# UI_Ticketing_Master.net
KiCad netlist of a schematic drawn in Altium Designer
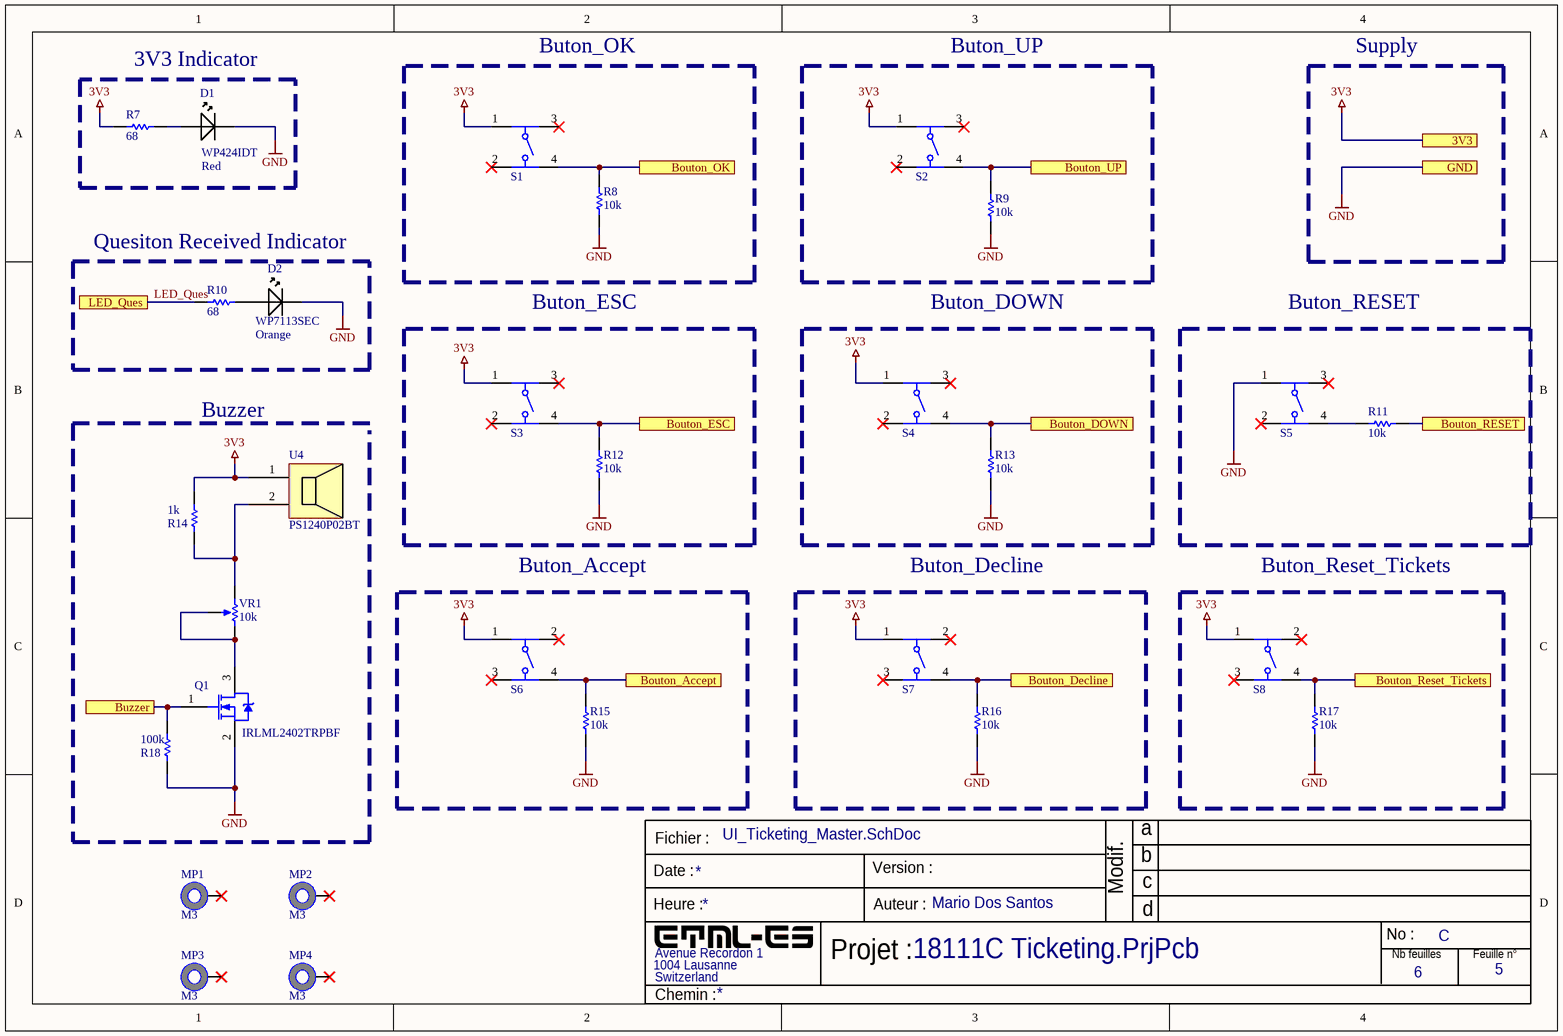
[diagram p0: UI_Ticketing_Master.SchDoc]

(export (version "E")
  (design (tool "Eeschema 10.0.6"))
  (components
    (comp (ref "D1")
      (value "WP424IDT")
      (footprint "LED-2P-2.28-3MM")
      (description "LED")
      (fields (field (name "COLOR") "Red"))
      (libsource (lib "") (part "LED_1"))
    )
    (comp (ref "D2")
      (value "WP7113SEC")
      (footprint "Type 5mm")
      (description "LED")
      (fields (field (name "COLOR") "Orange"))
      (libsource (lib "Spectrometre_Lib") (part "LED"))
    )
    (comp (ref "MP1")
      (value "M3")
      (footprint "PCB_Ticketing_Master:9774010151")
      (description "WA-SMSI SMT Steel Spacer, M2.5 Thread Internal, Length 1mm")
      (libsource (lib "ALTIUM-SMSI_SMT_STEEL_SPACER_M2_5_THREAD_INTERNAL-rev16b") (part "9774010151"))
    )
    (comp (ref "MP2")
      (value "M3")
      (footprint "PCB_Ticketing_Master:9774010151")
      (description "WA-SMSI SMT Steel Spacer, M2.5 Thread Internal, Length 1mm")
      (libsource (lib "ALTIUM-SMSI_SMT_STEEL_SPACER_M2_5_THREAD_INTERNAL-rev16b") (part "9774010151"))
    )
    (comp (ref "MP3")
      (value "M3")
      (footprint "PCB_Ticketing_Master:9774010151")
      (description "WA-SMSI SMT Steel Spacer, M2.5 Thread Internal, Length 1mm")
      (libsource (lib "ALTIUM-SMSI_SMT_STEEL_SPACER_M2_5_THREAD_INTERNAL-rev16b") (part "9774010151"))
    )
    (comp (ref "MP4")
      (value "M3")
      (footprint "PCB_Ticketing_Master:9774010151")
      (description "WA-SMSI SMT Steel Spacer, M2.5 Thread Internal, Length 1mm")
      (libsource (lib "ALTIUM-SMSI_SMT_STEEL_SPACER_M2_5_THREAD_INTERNAL-rev16b") (part "9774010151"))
    )
    (comp (ref "Q1")
      (value "IRLML2402TRPBF")
      (footprint "INTR-IRLML2402TRPBF-3_V")
      (description "HEXFET(R) Power MOSFET, N-Channel, 20 V, 1.2 A, 3-Pin SOT-23, RoHS, Tape and Reel")
      (fields
        (field (name "MANUFACTURER") "Infineon Technologies")
        (field (name "PARTNUMBER") "IRLML2402TRBF")
      )
      (libsource (lib "Altium Content Vault") (part "CMP-2000-05155-1"))
    )
    (comp (ref "R7")
      (value "68")
      (footprint "RESC0805(2012)_L")
      (description "100K 0.125W 5% 0805 (2012 Metric)  SMD")
      (libsource (lib "Altium Content Vault") (part "CMP-1013-00122-1"))
    )
    (comp (ref "R8")
      (value "10k")
      (footprint "RESC0805(2012)_L")
      (description "100K 0.125W 5% 0805 (2012 Metric)  SMD")
      (fields (field (name "TOLERANCE") "5 %") (field (name "POWER") "0.125 W"))
      (libsource (lib "Altium Content Vault") (part "CMP-1013-00122-1"))
    )
    (comp (ref "R9")
      (value "10k")
      (footprint "RESC0805(2012)_L")
      (description "100K 0.125W 5% 0805 (2012 Metric)  SMD")
      (fields (field (name "TOLERANCE") "5 %") (field (name "POWER") "0.125 W"))
      (libsource (lib "Altium Content Vault") (part "CMP-1013-00122-1"))
    )
    (comp (ref "R10")
      (value "68")
      (footprint "RESC0805(2012)_L")
      (description "100K 0.125W 5% 0805 (2012 Metric)  SMD")
      (fields (field (name "TOLERANCE") "5 %") (field (name "POWER") "0.125 W"))
      (libsource (lib "Altium Content Vault") (part "CMP-1013-00122-1"))
    )
    (comp (ref "R11")
      (value "10k")
      (footprint "RESC0805(2012)_L")
      (description "100K 0.125W 5% 0805 (2012 Metric)  SMD")
      (fields (field (name "TOLERANCE") "5 %") (field (name "POWER") "0.125 W"))
      (libsource (lib "Altium Content Vault") (part "CMP-1013-00122-1"))
    )
    (comp (ref "R12")
      (value "10k")
      (footprint "RESC0805(2012)_L")
      (description "100K 0.125W 5% 0805 (2012 Metric)  SMD")
      (fields (field (name "TOLERANCE") "5 %") (field (name "POWER") "0.125 W"))
      (libsource (lib "Altium Content Vault") (part "CMP-1013-00122-1"))
    )
    (comp (ref "R13")
      (value "10k")
      (footprint "RESC0805(2012)_L")
      (description "100K 0.125W 5% 0805 (2012 Metric)  SMD")
      (fields (field (name "TOLERANCE") "5 %") (field (name "POWER") "0.125 W"))
      (libsource (lib "Altium Content Vault") (part "CMP-1013-00122-1"))
    )
    (comp (ref "R14")
      (value "1k")
      (footprint "RESC2013X60X35ML10T20")
      (description "Chip Resistor, 1 KOhm, +/- 1%, 125 mW, -55 to 155 degC, 0805 (2012 Metric), RoHS, Tape and Reel")
      (libsource (lib "Altium Content Vault") (part "CMP-2100-03671-1"))
    )
    (comp (ref "R15")
      (value "10k")
      (footprint "RESC0805(2012)_L")
      (description "100K 0.125W 5% 0805 (2012 Metric)  SMD")
      (fields (field (name "TOLERANCE") "5 %") (field (name "POWER") "0.125 W"))
      (libsource (lib "Altium Content Vault") (part "CMP-1013-00122-1"))
    )
    (comp (ref "R16")
      (value "10k")
      (footprint "RESC0805(2012)_L")
      (description "100K 0.125W 5% 0805 (2012 Metric)  SMD")
      (fields (field (name "TOLERANCE") "5 %") (field (name "POWER") "0.125 W"))
      (libsource (lib "Altium Content Vault") (part "CMP-1013-00122-1"))
    )
    (comp (ref "R17")
      (value "10k")
      (footprint "RESC0805(2012)_L")
      (description "100K 0.125W 5% 0805 (2012 Metric)  SMD")
      (fields (field (name "TOLERANCE") "5 %") (field (name "POWER") "0.125 W"))
      (libsource (lib "Altium Content Vault") (part "CMP-1013-00122-1"))
    )
    (comp (ref "R18")
      (value "100k")
      (footprint "RESC2013X60X35ML10T20")
      (description "Chip Resistor, 100 KOhm, +/- 1%, 125 mW, -55 to 155 degC, 0805 (2012 Metric), RoHS, Tape and Reel")
      (libsource (lib "Altium Content Vault") (part "CMP-2100-03671-1"))
    )
    (comp (ref "S1")
      (value "430152095826")
      (footprint "430152095826")
      (description "6x6mm SMD Tact Switch WS-TASV, height 9.5 mm, 260 gf")
      (fields (field (name "PART NUMBER") "732-6999-1-ND") (field (name "PUBLISHER") "Wurth Elektronik"))
      (libsource (lib "ALTIUM-WS-TASV-rev17b") (part "430152095826"))
    )
    (comp (ref "S2")
      (value "430152095826")
      (footprint "430152095826")
      (description "6x6mm SMD Tact Switch WS-TASV, height 9.5 mm, 260 gf")
      (fields (field (name "PART NUMBER") "732-6999-1-ND") (field (name "PUBLISHER") "Wurth Elektronik"))
      (libsource (lib "ALTIUM-WS-TASV-rev17b") (part "430152095826"))
    )
    (comp (ref "S3")
      (value "430152095826")
      (footprint "430152095826")
      (description "6x6mm SMD Tact Switch WS-TASV, height 9.5 mm, 260 gf")
      (fields (field (name "PART NUMBER") "732-6999-1-ND") (field (name "PUBLISHER") "Wurth Elektronik"))
      (libsource (lib "ALTIUM-WS-TASV-rev17b") (part "430152095826"))
    )
    (comp (ref "S4")
      (value "430152095826")
      (footprint "430152095826")
      (description "6x6mm SMD Tact Switch WS-TASV, height 9.5 mm, 260 gf")
      (fields (field (name "PART NUMBER") "732-6999-1-ND") (field (name "PUBLISHER") "Wurth Elektronik"))
      (libsource (lib "ALTIUM-WS-TASV-rev17b") (part "430152095826"))
    )
    (comp (ref "S5")
      (value "430182050816")
      (footprint "430182050816")
      (description "6x6mm SMD Tact Switch WS-TASV, height 5 mm, 160 gf")
      (fields (field (name "PART NUMBER") "732-7005-1-ND") (field (name "PUBLISHER") "Wurth Elektronik"))
      (libsource (lib "ALTIUM-WS-TASV-rev17b") (part "430182050816"))
    )
    (comp (ref "S6")
      (value "430466073726")
      (footprint "4304x60737x6_12x12x7.3")
      (description "WS-TATV 12x12mm washable Tact Switch, THT version")
      (fields (field (name "PART NUMBER") "430466073726-ND") (field (name "PUBLISHER") "Wurth Elektronik"))
      (libsource (lib "ALTIUM-WS-TATV-rev17a") (part "430466073726"))
    )
    (comp (ref "S7")
      (value "430466073726")
      (footprint "4304x60737x6_12x12x7.3")
      (description "WS-TATV 12x12mm washable Tact Switch, THT version")
      (fields (field (name "PART NUMBER") "430466073726-ND") (field (name "PUBLISHER") "Wurth Elektronik"))
      (libsource (lib "ALTIUM-WS-TATV-rev17a") (part "430466073726"))
    )
    (comp (ref "S8")
      (value "430466073726")
      (footprint "4304x60737x6_12x12x7.3")
      (description "WS-TATV 12x12mm washable Tact Switch, THT version")
      (fields (field (name "PART NUMBER") "430466073726-ND") (field (name "PUBLISHER") "Wurth Elektronik"))
      (libsource (lib "ALTIUM-WS-TATV-rev17a") (part "430466073726"))
    )
    (comp (ref "U4")
      (value "PS1240P02BT")
      (footprint "Buzzer")
      (description "Buzzer 12mm piezo")
      (fields (field (name "MANUFACTURER") "TDK Corporation"))
      (libsource (lib "Schlib1") (part "BZR"))
    )
    (comp (ref "VR1")
      (value "10k")
      (footprint "BOUR-3362P")
      (description "Square Trimpot(R) Trimming Potentiometer, 100 KOhm, 300 V, -55 to 125 degC, 3-Pin THD, RoHS, Tube")
      (fields (field (name "TOLERANCE") "1%") (field (name "PART NUMBER") "3362P-103LF-ND"))
      (libsource (lib "Altium Content Vault") (part "CMP-1747-00003-1"))
    )
  )
  (nets
    (net (code "1") (name "/Bouton_Accept") (class "Default")
      (node (ref "R15") (pin "1") (pinfunction "1_1") (pintype "passive"))
      (node (ref "S6") (pin "4") (pinfunction "4_4") (pintype "passive"))
    )
    (net (code "2") (name "/Bouton_DOWN") (class "Default")
      (node (ref "R13") (pin "1") (pinfunction "1_1") (pintype "passive"))
      (node (ref "S4") (pin "4") (pinfunction "4_4") (pintype "passive"))
    )
    (net (code "3") (name "/Bouton_Decline") (class "Default")
      (node (ref "R16") (pin "1") (pinfunction "1_1") (pintype "passive"))
      (node (ref "S7") (pin "4") (pinfunction "4_4") (pintype "passive"))
    )
    (net (code "4") (name "/Bouton_ESC") (class "Default")
      (node (ref "R12") (pin "1") (pinfunction "1_1") (pintype "passive"))
      (node (ref "S3") (pin "4") (pinfunction "4_4") (pintype "passive"))
    )
    (net (code "5") (name "/Bouton_OK") (class "Default")
      (node (ref "R8") (pin "1") (pinfunction "1_1") (pintype "passive"))
      (node (ref "S1") (pin "4") (pinfunction "4_4") (pintype "passive"))
    )
    (net (code "6") (name "/Bouton_RESET") (class "Default")
      (node (ref "R11") (pin "2") (pinfunction "2_2") (pintype "passive"))
    )
    (net (code "7") (name "/Bouton_Reset_Tickets") (class "Default")
      (node (ref "R17") (pin "1") (pinfunction "1_1") (pintype "passive"))
      (node (ref "S8") (pin "4") (pinfunction "4_4") (pintype "passive"))
    )
    (net (code "8") (name "/Bouton_UP") (class "Default")
      (node (ref "R9") (pin "1") (pinfunction "1_1") (pintype "passive"))
      (node (ref "S2") (pin "4") (pinfunction "4_4") (pintype "passive"))
    )
    (net (code "9") (name "/Buzzer") (class "Default")
      (node (ref "Q1") (pin "1") (pinfunction "G_1") (pintype "passive"))
      (node (ref "R18") (pin "2") (pinfunction "2_2") (pintype "passive"))
    )
    (net (code "10") (name "/LED_Ques") (class "Default")
      (node (ref "R10") (pin "2") (pinfunction "2_2") (pintype "passive"))
    )
    (net (code "11") (name "3V3") (class "Default")
      (node (ref "R14") (pin "2") (pinfunction "2_2") (pintype "passive"))
      (node (ref "R7") (pin "2") (pinfunction "2_2") (pintype "passive"))
      (node (ref "S1") (pin "1") (pinfunction "1_1") (pintype "passive"))
      (node (ref "S2") (pin "1") (pinfunction "1_1") (pintype "passive"))
      (node (ref "S3") (pin "1") (pinfunction "1_1") (pintype "passive"))
      (node (ref "S4") (pin "1") (pinfunction "1_1") (pintype "passive"))
      (node (ref "S6") (pin "1") (pinfunction "1_1") (pintype "passive"))
      (node (ref "S7") (pin "1") (pinfunction "1_1") (pintype "passive"))
      (node (ref "S8") (pin "1") (pinfunction "1_1") (pintype "passive"))
      (node (ref "U4") (pin "1") (pintype "passive"))
    )
    (net (code "12") (name "GND") (class "Default")
      (node (ref "D1") (pin "2") (pinfunction "Cathode_2") (pintype "passive"))
      (node (ref "D2") (pin "1") (pinfunction "Cathode_1") (pintype "passive"))
      (node (ref "Q1") (pin "2") (pinfunction "S_2") (pintype "passive"))
      (node (ref "R12") (pin "2") (pinfunction "2_2") (pintype "passive"))
      (node (ref "R13") (pin "2") (pinfunction "2_2") (pintype "passive"))
      (node (ref "R15") (pin "2") (pinfunction "2_2") (pintype "passive"))
      (node (ref "R16") (pin "2") (pinfunction "2_2") (pintype "passive"))
      (node (ref "R17") (pin "2") (pinfunction "2_2") (pintype "passive"))
      (node (ref "R18") (pin "1") (pinfunction "1_1") (pintype "passive"))
      (node (ref "R8") (pin "2") (pinfunction "2_2") (pintype "passive"))
      (node (ref "R9") (pin "2") (pinfunction "2_2") (pintype "passive"))
      (node (ref "S5") (pin "1") (pinfunction "1_1") (pintype "passive"))
    )
    (net (code "13") (name "Net-(D1-Anode)") (class "Default")
      (node (ref "D1") (pin "1") (pinfunction "Anode_1") (pintype "passive"))
      (node (ref "R7") (pin "1") (pinfunction "1_1") (pintype "passive"))
    )
    (net (code "14") (name "Net-(D2-Anode)") (class "Default")
      (node (ref "D2") (pin "2") (pinfunction "Anode_2") (pintype "passive"))
      (node (ref "R10") (pin "1") (pinfunction "1_1") (pintype "passive"))
    )
    (net (code "15") (name "Net-(Q1-D)") (class "Default")
      (node (ref "Q1") (pin "3") (pinfunction "D_3") (pintype "passive"))
      (node (ref "VR1") (pin "2") (pinfunction "S_2") (pintype "passive"))
      (node (ref "VR1") (pin "3") (pinfunction "CW_3") (pintype "passive"))
    )
    (net (code "16") (name "Net-(R11-Pad1)") (class "Default")
      (node (ref "R11") (pin "1") (pinfunction "1_1") (pintype "passive"))
      (node (ref "S5") (pin "4") (pinfunction "4_4") (pintype "passive"))
    )
    (net (code "17") (name "Net-(VR1-CCW)") (class "Default")
      (node (ref "R14") (pin "1") (pinfunction "1_1") (pintype "passive"))
      (node (ref "U4") (pin "2") (pintype "passive"))
      (node (ref "VR1") (pin "1") (pinfunction "CCW_1") (pintype "passive"))
    )
    (net (code "18") (name "unconnected-(MP1-Pad1)") (class "Default")
      (node (ref "MP1") (pin "1") (pinfunction "1_1") (pintype "passive+no_connect"))
    )
    (net (code "19") (name "unconnected-(MP2-Pad1)") (class "Default")
      (node (ref "MP2") (pin "1") (pinfunction "1_1") (pintype "passive+no_connect"))
    )
    (net (code "20") (name "unconnected-(MP3-Pad1)") (class "Default")
      (node (ref "MP3") (pin "1") (pinfunction "1_1") (pintype "passive+no_connect"))
    )
    (net (code "21") (name "unconnected-(MP4-Pad1)") (class "Default")
      (node (ref "MP4") (pin "1") (pinfunction "1_1") (pintype "passive+no_connect"))
    )
    (net (code "22") (name "unconnected-(S1-Pad2)") (class "Default")
      (node (ref "S1") (pin "2") (pinfunction "2_2") (pintype "passive+no_connect"))
    )
    (net (code "23") (name "unconnected-(S1-Pad3)") (class "Default")
      (node (ref "S1") (pin "3") (pinfunction "3_3") (pintype "passive+no_connect"))
    )
    (net (code "24") (name "unconnected-(S2-Pad2)") (class "Default")
      (node (ref "S2") (pin "2") (pinfunction "2_2") (pintype "passive+no_connect"))
    )
    (net (code "25") (name "unconnected-(S2-Pad3)") (class "Default")
      (node (ref "S2") (pin "3") (pinfunction "3_3") (pintype "passive+no_connect"))
    )
    (net (code "26") (name "unconnected-(S3-Pad2)") (class "Default")
      (node (ref "S3") (pin "2") (pinfunction "2_2") (pintype "passive+no_connect"))
    )
    (net (code "27") (name "unconnected-(S3-Pad3)") (class "Default")
      (node (ref "S3") (pin "3") (pinfunction "3_3") (pintype "passive+no_connect"))
    )
    (net (code "28") (name "unconnected-(S4-Pad2)") (class "Default")
      (node (ref "S4") (pin "2") (pinfunction "2_2") (pintype "passive+no_connect"))
    )
    (net (code "29") (name "unconnected-(S4-Pad3)") (class "Default")
      (node (ref "S4") (pin "3") (pinfunction "3_3") (pintype "passive+no_connect"))
    )
    (net (code "30") (name "unconnected-(S5-Pad2)") (class "Default")
      (node (ref "S5") (pin "2") (pinfunction "2_2") (pintype "passive+no_connect"))
    )
    (net (code "31") (name "unconnected-(S5-Pad3)") (class "Default")
      (node (ref "S5") (pin "3") (pinfunction "3_3") (pintype "passive+no_connect"))
    )
    (net (code "32") (name "unconnected-(S6-Pad2)") (class "Default")
      (node (ref "S6") (pin "2") (pinfunction "2_2") (pintype "passive+no_connect"))
    )
    (net (code "33") (name "unconnected-(S6-Pad3)") (class "Default")
      (node (ref "S6") (pin "3") (pinfunction "3_3") (pintype "passive+no_connect"))
    )
    (net (code "34") (name "unconnected-(S7-Pad2)") (class "Default")
      (node (ref "S7") (pin "2") (pinfunction "2_2") (pintype "passive+no_connect"))
    )
    (net (code "35") (name "unconnected-(S7-Pad3)") (class "Default")
      (node (ref "S7") (pin "3") (pinfunction "3_3") (pintype "passive+no_connect"))
    )
    (net (code "36") (name "unconnected-(S8-Pad2)") (class "Default")
      (node (ref "S8") (pin "2") (pinfunction "2_2") (pintype "passive+no_connect"))
    )
    (net (code "37") (name "unconnected-(S8-Pad3)") (class "Default")
      (node (ref "S8") (pin "3") (pinfunction "3_3") (pintype "passive+no_connect"))
    )
  )
)
